# logic_lcd.net
KiCad netlist of a schematic drawn in Altium Designer
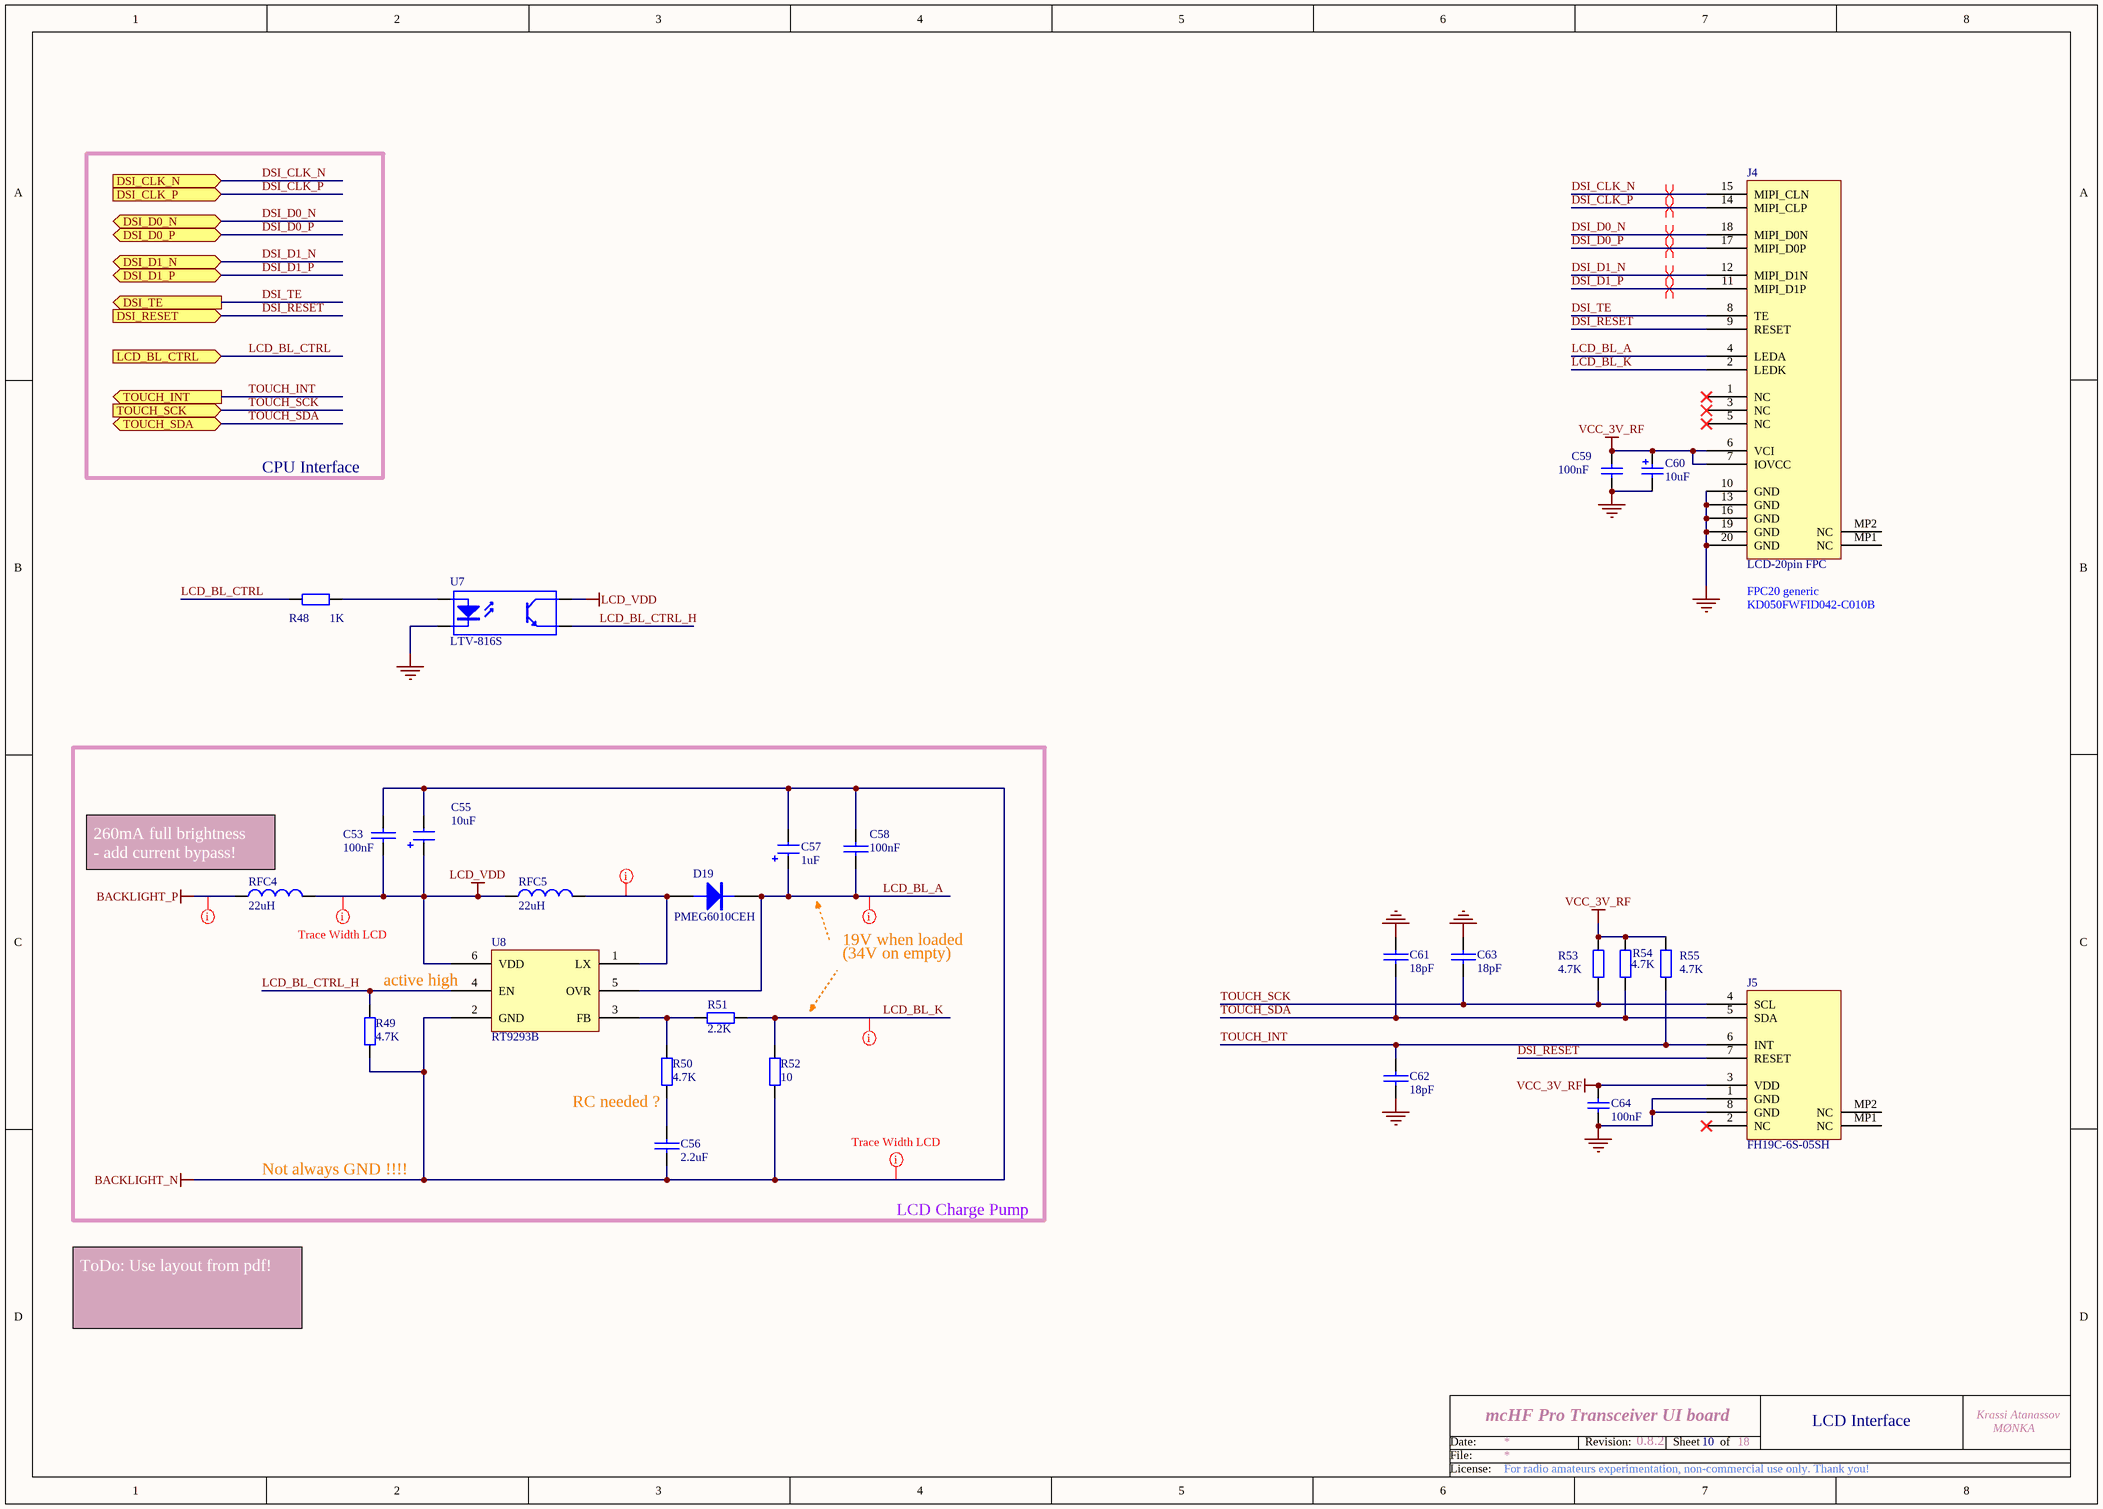
[diagram p0: logic_lcd.SchDoc]

(export (version "E")
  (design (tool "Eeschema 10.0.6"))
  (components
    (comp (ref "C53")
      (value "100nF")
      (footprint "0805")
      (description "Capacitor")
      (libsource (lib "mcHF_ui") (part "CAP"))
    )
    (comp (ref "C55")
      (value "10uF")
      (footprint "1206_Elec_Cap")
      (description "Electrolitic capacitor")
      (libsource (lib "mcHF_ui") (part "CAP-POL"))
    )
    (comp (ref "C56")
      (value "2.2uF")
      (footprint "0805")
      (description "Ceramic Capacitor")
      (libsource (lib "mcHF_ui") (part "CAP"))
    )
    (comp (ref "C57")
      (value "1uF")
      (footprint "1206_Elec_Cap")
      (description "Electrolitic capacitor")
      (fields (field (name "VOLTAGE") "50V"))
      (libsource (lib "mcHF_ui") (part "CAP-POL"))
    )
    (comp (ref "C58")
      (value "100nF")
      (footprint "0805")
      (description "Capacitor")
      (libsource (lib "mcHF_ui") (part "CAP"))
    )
    (comp (ref "C59")
      (value "100nF")
      (footprint "0805")
      (description "Capacitor")
      (fields (field (name "PUBLISHER") "Altium Limited"))
      (libsource (lib "Miscellaneous Devices") (part "CAP"))
    )
    (comp (ref "C60")
      (value "10uF")
      (footprint "1206_Elec_Cap")
      (fields (field (name "PUBLISHER") "Altium Limited"))
      (libsource (lib "Miscellaneous Devices") (part "Cap Pol1"))
    )
    (comp (ref "C61")
      (value "18pF")
      (footprint "0805")
      (description "Capacitor")
      (fields (field (name "VOLTAGE") "100V"))
      (libsource (lib "mcHF_rf") (part "CAP"))
    )
    (comp (ref "C62")
      (value "18pF")
      (footprint "0805")
      (description "Capacitor")
      (fields (field (name "VOLTAGE") "100V"))
      (libsource (lib "mcHF_rf") (part "CAP"))
    )
    (comp (ref "C63")
      (value "18pF")
      (footprint "0805")
      (description "Capacitor")
      (fields (field (name "VOLTAGE") "100V"))
      (libsource (lib "mcHF_rf") (part "CAP"))
    )
    (comp (ref "C64")
      (value "100nF")
      (footprint "0805")
      (description "Capacitor")
      (fields (field (name "PUBLISHER") "Altium Limited"))
      (libsource (lib "Miscellaneous Devices") (part "CAP"))
    )
    (comp (ref "D19")
      (value "PMEG6010CEH")
      (footprint "SOD87")
      (description "DIODE, SCHOTTKY, 1A, 60V, SOD-123F")
      (libsource (lib "mcHF_rf") (part "PMEG6010CEH"))
    )
    (comp (ref "J4")
      (value "LCD-20pin FPC")
      (footprint "MOLX-52746-2071")
      (description "LCD-20pin FPC, Top contacts position")
      (libsource (lib "__ui") (part "KD050FWFID042-C010B"))
    )
    (comp (ref "J5")
      (value "FH19C-6S-05SH")
      (footprint "MOLX-501461-0891")
      (description "8 pin FPC, Top contacts position")
      (libsource (lib "__ui") (part "FPC8"))
    )
    (comp (ref "R48")
      (value "1K")
      (footprint "0805")
      (description "Resistor")
      (libsource (lib "mcHF_rf") (part "RES"))
    )
    (comp (ref "R49")
      (value "4.7K")
      (footprint "0805")
      (description "Resistor")
      (libsource (lib "mcHF_ui") (part "RES"))
    )
    (comp (ref "R50")
      (value "4.7K")
      (footprint "0805")
      (description "Resistor")
      (libsource (lib "mcHF_ui") (part "RES"))
    )
    (comp (ref "R51")
      (value "2.2K")
      (footprint "0805")
      (description "Resistor")
      (libsource (lib "") (part "RES_1"))
    )
    (comp (ref "R52")
      (value "10")
      (footprint "1206")
      (description "Resistor")
      (libsource (lib "mcHF_ui") (part "RES"))
    )
    (comp (ref "R53")
      (value "4.7K")
      (footprint "0805")
      (description "Resistor")
      (libsource (lib "*") (part "RES"))
    )
    (comp (ref "R54")
      (value "4.7K")
      (footprint "0805")
      (description "Resistor")
      (libsource (lib "*") (part "RES"))
    )
    (comp (ref "R55")
      (value "4.7K")
      (footprint "0805")
      (description "Resistor")
      (libsource (lib "*") (part "RES"))
    )
    (comp (ref "RFC4")
      (value "22uH")
      (footprint "0805")
      (description "Power Inductor")
      (libsource (lib "mcHF_ui") (part "Inductor"))
    )
    (comp (ref "RFC5")
      (value "22uH")
      (footprint "0805")
      (description "Power Inductor")
      (libsource (lib "mcHF_ui") (part "Inductor"))
    )
    (comp (ref "U7")
      (value "LTV-816S")
      (footprint "SMDIP-4_new1")
      (description "OPTOCOUPLER, SMDIP-4, TR O/P")
      (libsource (lib "mcHF_rf") (part "ISP817XSM"))
    )
    (comp (ref "U8")
      (value "RT9293B")
      (footprint "SOT25-6")
      (description "Charge Pump")
      (libsource (lib "mcHF_ui_b") (part "RT9293B"))
    )
  )
  (nets
    (net (code "1") (name "/DSI_CLK_N") (class "Default")
      (node (ref "J4") (pin "15") (pinfunction "MIPI_CLN_15") (pintype "passive"))
    )
    (net (code "2") (name "/DSI_CLK_P") (class "Default")
      (node (ref "J4") (pin "14") (pinfunction "MIPI_CLP_14") (pintype "passive"))
    )
    (net (code "3") (name "/DSI_D0_N") (class "Default")
      (node (ref "J4") (pin "18") (pinfunction "MIPI_D0N_18") (pintype "passive"))
    )
    (net (code "4") (name "/DSI_D0_P") (class "Default")
      (node (ref "J4") (pin "17") (pinfunction "MIPI_D0P_17") (pintype "passive"))
    )
    (net (code "5") (name "/DSI_D1_N") (class "Default")
      (node (ref "J4") (pin "12") (pinfunction "MIPI_D1N_12") (pintype "passive"))
    )
    (net (code "6") (name "/DSI_D1_P") (class "Default")
      (node (ref "J4") (pin "11") (pinfunction "MIPI_D1P_11") (pintype "passive"))
    )
    (net (code "7") (name "/DSI_RESET") (class "Default")
      (node (ref "J4") (pin "9") (pinfunction "RESET_9") (pintype "passive"))
      (node (ref "J5") (pin "7") (pinfunction "RESET_7") (pintype "passive"))
    )
    (net (code "8") (name "/DSI_TE") (class "Default")
      (node (ref "J4") (pin "8") (pinfunction "TE_8") (pintype "passive"))
    )
    (net (code "9") (name "/LCD_BL_A") (class "Default")
      (node (ref "C57") (pin "1") (pinfunction "1_1") (pintype "passive"))
      (node (ref "C58") (pin "2") (pinfunction "2_2") (pintype "passive"))
      (node (ref "D19") (pin "2") (pinfunction "K_2") (pintype "passive"))
      (node (ref "J4") (pin "4") (pinfunction "LEDA_4") (pintype "passive"))
      (node (ref "U8") (pin "5") (pinfunction "OVR_5") (pintype "passive"))
    )
    (net (code "10") (name "/LCD_BL_CTRL") (class "Default")
      (node (ref "R48") (pin "1") (pinfunction "1_1") (pintype "passive"))
    )
    (net (code "11") (name "/LCD_BL_CTRL_H") (class "Default")
      (node (ref "R49") (pin "2") (pinfunction "2_2") (pintype "passive"))
      (node (ref "U7") (pin "3") (pinfunction "E_3") (pintype "passive"))
      (node (ref "U8") (pin "4") (pinfunction "EN_4") (pintype "passive"))
    )
    (net (code "12") (name "/LCD_BL_K") (class "Default")
      (node (ref "J4") (pin "2") (pinfunction "LEDK_2") (pintype "passive"))
      (node (ref "R51") (pin "2") (pinfunction "2_2") (pintype "passive"))
      (node (ref "R52") (pin "2") (pinfunction "2_2") (pintype "passive"))
    )
    (net (code "13") (name "/TOUCH_INT") (class "Default")
      (node (ref "C62") (pin "1") (pinfunction "1_1") (pintype "passive"))
      (node (ref "J5") (pin "6") (pinfunction "INT_6") (pintype "passive"))
      (node (ref "R55") (pin "2") (pinfunction "2_2") (pintype "passive"))
    )
    (net (code "14") (name "/TOUCH_SCK") (class "Default")
      (node (ref "C63") (pin "2") (pinfunction "2_2") (pintype "passive"))
      (node (ref "J5") (pin "4") (pinfunction "SCL_4") (pintype "passive"))
      (node (ref "R53") (pin "2") (pinfunction "2_2") (pintype "passive"))
    )
    (net (code "15") (name "/TOUCH_SDA") (class "Default")
      (node (ref "C61") (pin "2") (pinfunction "2_2") (pintype "passive"))
      (node (ref "J5") (pin "5") (pinfunction "SDA_5") (pintype "passive"))
      (node (ref "R54") (pin "2") (pinfunction "2_2") (pintype "passive"))
    )
    (net (code "16") (name "BACKLIGHT_N") (class "Default")
      (node (ref "C53") (pin "1") (pinfunction "1_1") (pintype "passive"))
      (node (ref "C55") (pin "2") (pinfunction "2_2") (pintype "passive"))
      (node (ref "C56") (pin "2") (pinfunction "2_2") (pintype "passive"))
      (node (ref "C57") (pin "2") (pinfunction "2_2") (pintype "passive"))
      (node (ref "C58") (pin "1") (pinfunction "1_1") (pintype "passive"))
      (node (ref "R49") (pin "1") (pinfunction "1_1") (pintype "passive"))
      (node (ref "R52") (pin "1") (pinfunction "1_1") (pintype "passive"))
      (node (ref "U8") (pin "2") (pinfunction "GND_2") (pintype "passive"))
    )
    (net (code "17") (name "BACKLIGHT_P") (class "Default")
      (node (ref "RFC4") (pin "1") (pinfunction "1_1") (pintype "passive"))
    )
    (net (code "18") (name "GND") (class "Default")
      (node (ref "C59") (pin "1") (pinfunction "1_1") (pintype "passive"))
      (node (ref "C60") (pin "2") (pinfunction "2_2") (pintype "passive"))
      (node (ref "C61") (pin "1") (pinfunction "1_1") (pintype "passive"))
      (node (ref "C62") (pin "2") (pinfunction "2_2") (pintype "passive"))
      (node (ref "C63") (pin "1") (pinfunction "1_1") (pintype "passive"))
      (node (ref "C64") (pin "1") (pinfunction "1_1") (pintype "passive"))
      (node (ref "J4") (pin "10") (pinfunction "GND_10") (pintype "passive"))
      (node (ref "J4") (pin "13") (pinfunction "GND_13") (pintype "passive"))
      (node (ref "J4") (pin "16") (pinfunction "GND_16") (pintype "passive"))
      (node (ref "J4") (pin "19") (pinfunction "GND_19") (pintype "passive"))
      (node (ref "J4") (pin "20") (pinfunction "GND_20") (pintype "passive"))
      (node (ref "J5") (pin "1") (pinfunction "GND_1") (pintype "passive"))
      (node (ref "J5") (pin "8") (pinfunction "GND_8") (pintype "passive"))
      (node (ref "U7") (pin "2") (pinfunction "K_2") (pintype "passive"))
    )
    (net (code "19") (name "LCD_VDD") (class "Default")
      (node (ref "C53") (pin "2") (pinfunction "2_2") (pintype "passive"))
      (node (ref "C55") (pin "1") (pinfunction "1_1") (pintype "passive"))
      (node (ref "RFC4") (pin "2") (pinfunction "2_2") (pintype "passive"))
      (node (ref "RFC5") (pin "1") (pinfunction "1_1") (pintype "passive"))
      (node (ref "U7") (pin "4") (pinfunction "C_4") (pintype "passive"))
      (node (ref "U8") (pin "6") (pinfunction "VDD_6") (pintype "passive"))
    )
    (net (code "20") (name "Net-(C56-Pad1)") (class "Default")
      (node (ref "C56") (pin "1") (pinfunction "1_1") (pintype "passive"))
      (node (ref "R50") (pin "1") (pinfunction "1_1") (pintype "passive"))
    )
    (net (code "21") (name "Net-(D19-A)") (class "Default")
      (node (ref "D19") (pin "1") (pinfunction "A_1") (pintype "passive"))
      (node (ref "RFC5") (pin "2") (pinfunction "2_2") (pintype "passive"))
      (node (ref "U8") (pin "1") (pinfunction "LX_1") (pintype "passive"))
    )
    (net (code "22") (name "Net-(U7-A)") (class "Default")
      (node (ref "R48") (pin "2") (pinfunction "2_2") (pintype "passive"))
      (node (ref "U7") (pin "1") (pinfunction "A_1") (pintype "passive"))
    )
    (net (code "23") (name "Net-(U8-FB)") (class "Default")
      (node (ref "R50") (pin "2") (pinfunction "2_2") (pintype "passive"))
      (node (ref "R51") (pin "1") (pinfunction "1_1") (pintype "passive"))
      (node (ref "U8") (pin "3") (pinfunction "FB_3") (pintype "passive"))
    )
    (net (code "24") (name "VCC_3V_RF") (class "Default")
      (node (ref "C59") (pin "2") (pinfunction "2_2") (pintype "passive"))
      (node (ref "C60") (pin "1") (pinfunction "1_1") (pintype "passive"))
      (node (ref "C64") (pin "2") (pinfunction "2_2") (pintype "passive"))
      (node (ref "J4") (pin "6") (pinfunction "VCI_6") (pintype "passive"))
      (node (ref "J4") (pin "7") (pinfunction "IOVCC_7") (pintype "passive"))
      (node (ref "J5") (pin "3") (pinfunction "VDD_3") (pintype "passive"))
      (node (ref "R53") (pin "1") (pinfunction "1_1") (pintype "passive"))
      (node (ref "R54") (pin "1") (pinfunction "1_1") (pintype "passive"))
      (node (ref "R55") (pin "1") (pinfunction "1_1") (pintype "passive"))
    )
    (net (code "25") (name "unconnected-(J4-NC-Pad1)") (class "Default")
      (node (ref "J4") (pin "1") (pinfunction "NC_1") (pintype "passive+no_connect"))
    )
    (net (code "26") (name "unconnected-(J4-NC-Pad3)") (class "Default")
      (node (ref "J4") (pin "3") (pinfunction "NC_3") (pintype "passive+no_connect"))
    )
    (net (code "27") (name "unconnected-(J4-NC-Pad5)") (class "Default")
      (node (ref "J4") (pin "5") (pinfunction "NC_5") (pintype "passive+no_connect"))
    )
    (net (code "28") (name "unconnected-(J4-NC-PadMP1)") (class "Default")
      (node (ref "J4") (pin "MP1") (pinfunction "NC_MP1") (pintype "passive"))
    )
    (net (code "29") (name "unconnected-(J4-NC-PadMP2)") (class "Default")
      (node (ref "J4") (pin "MP2") (pinfunction "NC_MP2") (pintype "passive"))
    )
    (net (code "30") (name "unconnected-(J5-NC-Pad2)") (class "Default")
      (node (ref "J5") (pin "2") (pinfunction "NC_2") (pintype "passive+no_connect"))
    )
    (net (code "31") (name "unconnected-(J5-NC-PadMP1)") (class "Default")
      (node (ref "J5") (pin "MP1") (pinfunction "NC_MP1") (pintype "passive"))
    )
    (net (code "32") (name "unconnected-(J5-NC-PadMP2)") (class "Default")
      (node (ref "J5") (pin "MP2") (pinfunction "NC_MP2") (pintype "passive"))
    )
  )
)
